# ADC_RC_Network.net
KiCad netlist of a schematic drawn in Altium Designer
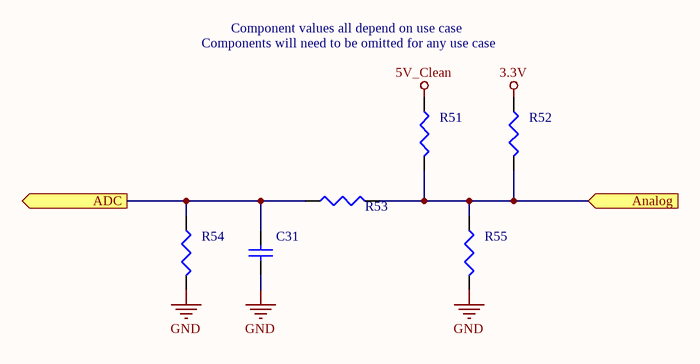
[diagram p0: ADC RC Network.SchDoc]

(export (version "E")
  (design (tool "Eeschema 10.0.6"))
  (components
    (comp (ref "C31")
      (value "Cap")
      (footprint "0603 to 0805 SMD")
      (description "Capacitor")
      (fields (field (name "PUBLISHER") "Altium Limited"))
      (libsource (lib "Miscellaneous Devices") (part "Cap"))
    )
    (comp (ref "R51")
      (value "Res3")
      (footprint "0603 to 0805 SMD")
      (description "Resistor")
      (fields (field (name "PUBLISHER") "Altium Limited"))
      (libsource (lib "Miscellaneous Devices") (part "Res3"))
    )
    (comp (ref "R52")
      (value "Res3")
      (footprint "0603 to 0805 SMD")
      (description "Resistor")
      (fields (field (name "PUBLISHER") "Altium Limited"))
      (libsource (lib "Miscellaneous Devices") (part "Res3"))
    )
    (comp (ref "R53")
      (value "Res3")
      (footprint "0603 to 0805 SMD")
      (description "Resistor")
      (fields (field (name "PUBLISHER") "Altium Limited"))
      (libsource (lib "Miscellaneous Devices") (part "Res3"))
    )
    (comp (ref "R54")
      (value "Res3")
      (footprint "0603 to 0805 SMD")
      (description "Resistor")
      (fields (field (name "PUBLISHER") "Altium Limited"))
      (libsource (lib "Miscellaneous Devices") (part "Res3"))
    )
    (comp (ref "R55")
      (value "Res3")
      (footprint "0603 to 0805 SMD")
      (description "Resistor")
      (fields (field (name "PUBLISHER") "Altium Limited"))
      (libsource (lib "Miscellaneous Devices") (part "Res3"))
    )
  )
  (nets
    (net (code "1") (name "/ADC") (class "Default")
      (node (ref "C31") (pin "2") (pinfunction "2_2") (pintype "passive"))
      (node (ref "R53") (pin "1") (pinfunction "1_1") (pintype "passive"))
      (node (ref "R54") (pin "1") (pinfunction "1_1") (pintype "passive"))
    )
    (net (code "2") (name "/Analog") (class "Default")
      (node (ref "R51") (pin "2") (pinfunction "2_2") (pintype "passive"))
      (node (ref "R52") (pin "2") (pinfunction "2_2") (pintype "passive"))
      (node (ref "R53") (pin "2") (pinfunction "2_2") (pintype "passive"))
      (node (ref "R55") (pin "1") (pinfunction "1_1") (pintype "passive"))
    )
    (net (code "3") (name "3.3V") (class "Default")
      (node (ref "R52") (pin "1") (pinfunction "1_1") (pintype "passive"))
    )
    (net (code "4") (name "5V_Clean") (class "Default")
      (node (ref "R51") (pin "1") (pinfunction "1_1") (pintype "passive"))
    )
    (net (code "5") (name "GND") (class "Default")
      (node (ref "C31") (pin "1") (pinfunction "1_1") (pintype "passive"))
      (node (ref "R54") (pin "2") (pinfunction "2_2") (pintype "passive"))
      (node (ref "R55") (pin "2") (pinfunction "2_2") (pintype "passive"))
    )
  )
)
